# SolderIronTemp.net
KiCad netlist of a schematic drawn in Altium Designer
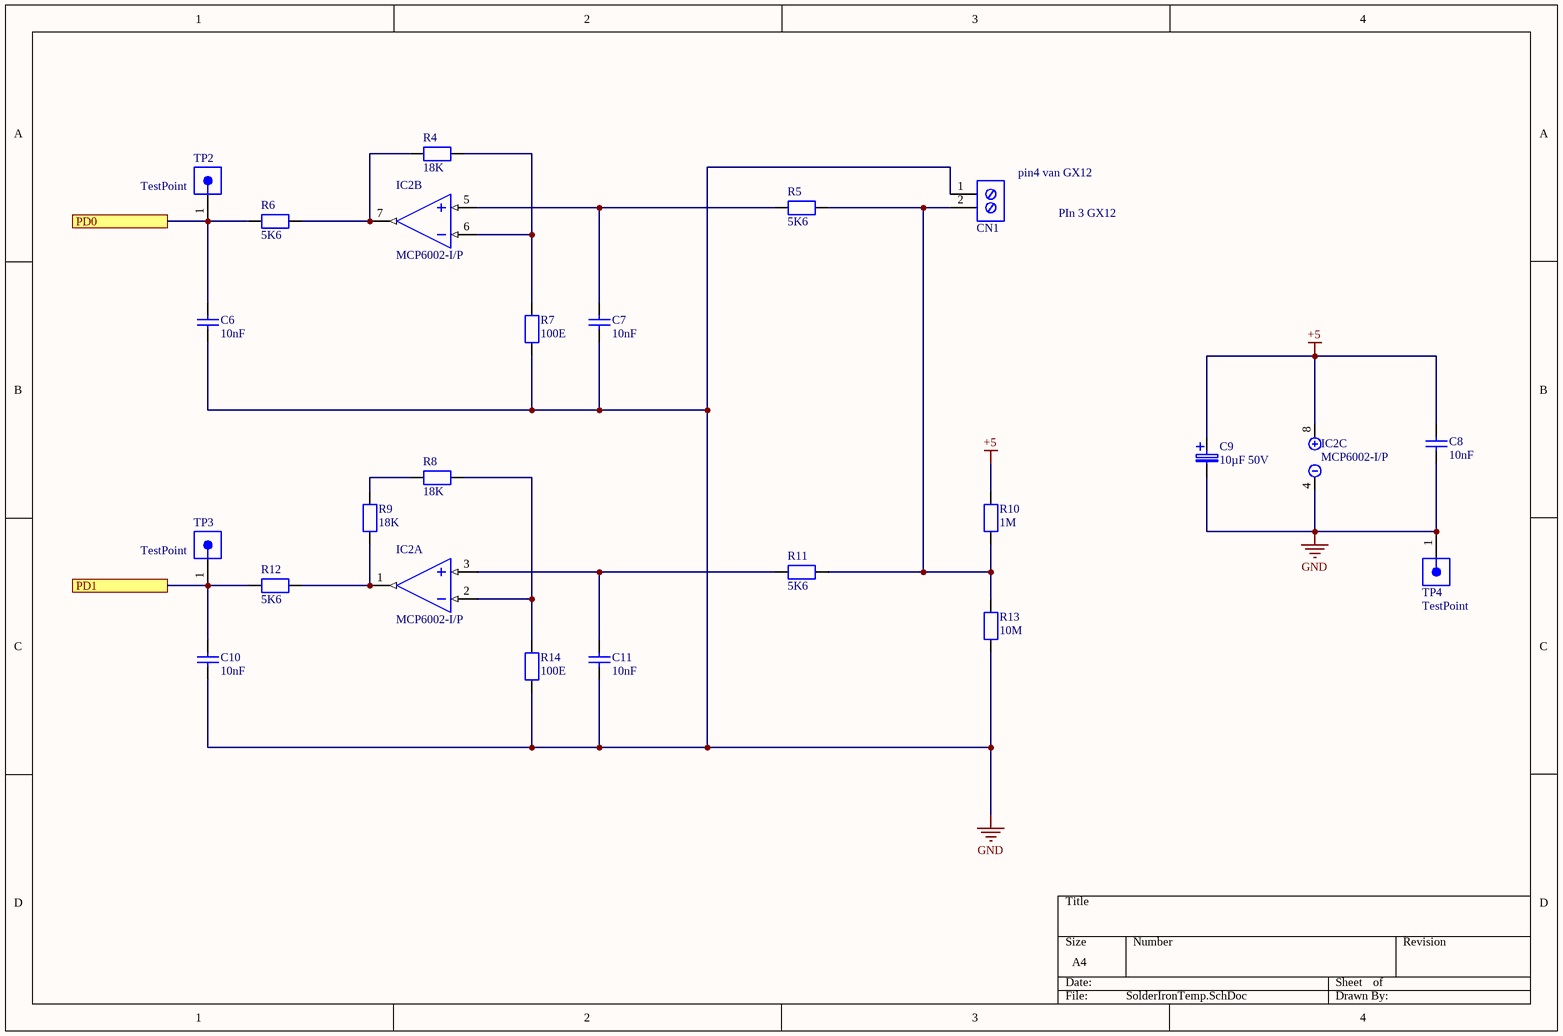
[diagram p0: SolderIronTemp.SchDoc]

(export (version "E")
  (design (tool "Eeschema 10.0.6"))
  (components
    (comp (ref "C6")
      (value "10nF")
      (footprint "CAPC2012X88N")
      (fields (field (name "MANUFACTURER") "Kemet") (field (name "PART NUMBER") "C0402C104K4RACTU"))
      (libsource (lib "SolderStation") (part "Capacitor ceramic 0805"))
    )
    (comp (ref "C7")
      (value "10nF")
      (footprint "CAPC2012X88N")
      (fields (field (name "MANUFACTURER") "Kemet") (field (name "PART NUMBER") "C0402C104K4RACTU"))
      (libsource (lib "SolderStation") (part "Capacitor ceramic 0805"))
    )
    (comp (ref "C8")
      (value "10nF")
      (footprint "CAPC2012X88N")
      (fields (field (name "MANUFACTURER") "Kemet") (field (name "PART NUMBER") "C0402C104K4RACTU"))
      (libsource (lib "SolderStation") (part "Capacitor ceramic 0805"))
    )
    (comp (ref "C9")
      (value "10µF 50V")
      (footprint "TAP106M050BRW")
      (description "Tantalum Capacitors - Solid Leaded 50V 10uF 20% ESR=1.6 Ohm TAP106M050BRW")
      (fields
        (field (name "MOUSER PART NUMBER") "581-TAP106M050BRW")
        (field (name "MANUFACTURER_PART_NUMBER") "TAP106M050BRW")
      )
      (libsource (lib "SolderStation") (part "capacitor THT radial tantalum"))
    )
    (comp (ref "C10")
      (value "10nF")
      (footprint "CAPC2012X88N")
      (fields (field (name "MANUFACTURER") "Kemet") (field (name "PART NUMBER") "C0402C104K4RACTU"))
      (libsource (lib "SolderStation") (part "Capacitor ceramic 0805"))
    )
    (comp (ref "C11")
      (value "10nF")
      (footprint "CAPC2012X88N")
      (fields (field (name "MANUFACTURER") "Kemet") (field (name "PART NUMBER") "C0402C104K4RACTU"))
      (libsource (lib "SolderStation") (part "Capacitor ceramic 0805"))
    )
    (comp (ref "CN1")
      (value "Printkroonsteen 2 POL")
      (footprint "Printkroonsteen 2pin")
      (description "Printkroonsteen 2 PO L1716020000")
      (fields
        (field (name "MANUFACTURER_PART_NUMBER") "1716020000")
        (field (name "MOUSER PART NUMBER") "470-1716020000")
      )
      (libsource (lib "SolderStation") (part "printkroonsteen 1 X 2"))
    )
    (comp (ref "IC2")
      (value "MCP6002-I/P")
      (footprint "PDIP300-P8")
      (description "Dual opamp")
      (libsource (lib "SolderStation") (part "CMP-0187-00119-3"))
    )
    (comp (ref "R4")
      (value "18K")
      (footprint "RESC2012X50N")
      (fields (field (name "MANUFACTURER") "Vishay Dale") (field (name "PART NUMBER") "CRCW08050000Z0EA"))
      (libsource (lib "SolderStation") (part "resistor 0805"))
    )
    (comp (ref "R5")
      (value "5K6")
      (footprint "RESC2012X50N")
      (fields (field (name "MANUFACTURER") "Vishay Dale") (field (name "PART NUMBER") "CRCW08050000Z0EA"))
      (libsource (lib "SolderStation") (part "resistor 0805"))
    )
    (comp (ref "R6")
      (value "5K6")
      (footprint "RESC2012X50N")
      (fields (field (name "MANUFACTURER") "Vishay Dale") (field (name "PART NUMBER") "CRCW08050000Z0EA"))
      (libsource (lib "SolderStation") (part "resistor 0805"))
    )
    (comp (ref "R7")
      (value "100E")
      (footprint "RESC2012X50N")
      (fields (field (name "MANUFACTURER") "Vishay Dale") (field (name "PART NUMBER") "CRCW08050000Z0EA"))
      (libsource (lib "SolderStation") (part "resistor 0805"))
    )
    (comp (ref "R8")
      (value "18K")
      (footprint "RESC2012X50N")
      (fields (field (name "MANUFACTURER") "Vishay Dale") (field (name "PART NUMBER") "CRCW08050000Z0EA"))
      (libsource (lib "SolderStation") (part "resistor 0805"))
    )
    (comp (ref "R9")
      (value "18K")
      (footprint "RESC2012X50N")
      (fields (field (name "MANUFACTURER") "Vishay Dale") (field (name "PART NUMBER") "CRCW08050000Z0EA"))
      (libsource (lib "SolderStation") (part "resistor 0805"))
    )
    (comp (ref "R10")
      (value "1M")
      (footprint "RESC2012X50N")
      (fields (field (name "MANUFACTURER") "Vishay Dale") (field (name "PART NUMBER") "CRCW08050000Z0EA"))
      (libsource (lib "SolderStation") (part "resistor 0805"))
    )
    (comp (ref "R11")
      (value "5K6")
      (footprint "RESC2012X50N")
      (fields (field (name "MANUFACTURER") "Vishay Dale") (field (name "PART NUMBER") "CRCW08050000Z0EA"))
      (libsource (lib "SolderStation") (part "resistor 0805"))
    )
    (comp (ref "R12")
      (value "5K6")
      (footprint "RESC2012X50N")
      (fields (field (name "MANUFACTURER") "Vishay Dale") (field (name "PART NUMBER") "CRCW08050000Z0EA"))
      (libsource (lib "SolderStation") (part "resistor 0805"))
    )
    (comp (ref "R13")
      (value "10M")
      (footprint "RESC2012X50N")
      (fields (field (name "MANUFACTURER") "Vishay Dale") (field (name "PART NUMBER") "CRCW08050000Z0EA"))
      (libsource (lib "SolderStation") (part "resistor 0805"))
    )
    (comp (ref "R14")
      (value "100E")
      (footprint "RESC2012X50N")
      (fields (field (name "MANUFACTURER") "Vishay Dale") (field (name "PART NUMBER") "CRCW08050000Z0EA"))
      (libsource (lib "SolderStation") (part "resistor 0805"))
    )
    (comp (ref "TP2")
      (value "TestPoint")
      (footprint "61300111121")
      (libsource (lib "SolderStation") (part "TestPoint"))
    )
    (comp (ref "TP3")
      (value "TestPoint")
      (footprint "61300111121")
      (libsource (lib "SolderStation") (part "TestPoint"))
    )
    (comp (ref "TP4")
      (value "TestPoint")
      (footprint "61300111121")
      (libsource (lib "SolderStation") (part "TestPoint"))
    )
  )
  (nets
    (net (code "1") (name "+5") (class "Default")
      (node (ref "C8") (pin "2") (pinfunction "2_2") (pintype "passive"))
      (node (ref "C9") (pin "1") (pinfunction "1_1") (pintype "passive"))
      (node (ref "IC2") (pin "8") (pinfunction "8_8") (pintype "passive"))
      (node (ref "R10") (pin "2") (pinfunction "2_2") (pintype "passive"))
    )
    (net (code "2") (name "/PD0") (class "Default")
      (node (ref "C6") (pin "2") (pinfunction "2_2") (pintype "passive"))
      (node (ref "R6") (pin "1") (pinfunction "1_1") (pintype "passive"))
      (node (ref "TP2") (pin "1") (pinfunction "1_1") (pintype "passive"))
    )
    (net (code "3") (name "/PD1") (class "Default")
      (node (ref "C10") (pin "2") (pinfunction "2_2") (pintype "passive"))
      (node (ref "R12") (pin "1") (pinfunction "1_1") (pintype "passive"))
      (node (ref "TP3") (pin "1") (pinfunction "1_1") (pintype "passive"))
    )
    (net (code "4") (name "GND") (class "Default")
      (node (ref "C10") (pin "1") (pinfunction "1_1") (pintype "passive"))
      (node (ref "C11") (pin "1") (pinfunction "1_1") (pintype "passive"))
      (node (ref "C6") (pin "1") (pinfunction "1_1") (pintype "passive"))
      (node (ref "C7") (pin "1") (pinfunction "1_1") (pintype "passive"))
      (node (ref "C8") (pin "1") (pinfunction "1_1") (pintype "passive"))
      (node (ref "C9") (pin "2") (pinfunction "2_2") (pintype "passive"))
      (node (ref "CN1") (pin "1") (pinfunction "1_1") (pintype "passive"))
      (node (ref "IC2") (pin "4") (pinfunction "4_4") (pintype "passive"))
      (node (ref "R13") (pin "1") (pinfunction "1_1") (pintype "passive"))
      (node (ref "R14") (pin "1") (pinfunction "1_1") (pintype "passive"))
      (node (ref "R7") (pin "1") (pinfunction "1_1") (pintype "passive"))
      (node (ref "TP4") (pin "1") (pinfunction "1_1") (pintype "passive"))
    )
    (net (code "5") (name "Net-(CN1-Pad2)") (class "Default")
      (node (ref "CN1") (pin "2") (pinfunction "2_2") (pintype "passive"))
      (node (ref "R10") (pin "1") (pinfunction "1_1") (pintype "passive"))
      (node (ref "R11") (pin "2") (pinfunction "2_2") (pintype "passive"))
      (node (ref "R13") (pin "2") (pinfunction "2_2") (pintype "passive"))
      (node (ref "R5") (pin "2") (pinfunction "2_2") (pintype "passive"))
    )
    (net (code "6") (name "Net-(IC2A-VINA+)") (class "Default")
      (node (ref "C11") (pin "2") (pinfunction "2_2") (pintype "passive"))
      (node (ref "IC2") (pin "3") (pinfunction "VINA+_3") (pintype "input"))
      (node (ref "R11") (pin "1") (pinfunction "1_1") (pintype "passive"))
    )
    (net (code "7") (name "Net-(IC2A-VINA-)") (class "Default")
      (node (ref "IC2") (pin "2") (pinfunction "VINA-_2") (pintype "input"))
      (node (ref "R14") (pin "2") (pinfunction "2_2") (pintype "passive"))
      (node (ref "R8") (pin "2") (pinfunction "2_2") (pintype "passive"))
    )
    (net (code "8") (name "Net-(IC2A-VOUTA)") (class "Default")
      (node (ref "IC2") (pin "1") (pinfunction "VOUTA_1") (pintype "output"))
      (node (ref "R12") (pin "2") (pinfunction "2_2") (pintype "passive"))
      (node (ref "R9") (pin "1") (pinfunction "1_1") (pintype "passive"))
    )
    (net (code "9") (name "Net-(IC2B-VINB+)") (class "Default")
      (node (ref "C7") (pin "2") (pinfunction "2_2") (pintype "passive"))
      (node (ref "IC2") (pin "5") (pinfunction "VINB+_5") (pintype "input"))
      (node (ref "R5") (pin "1") (pinfunction "1_1") (pintype "passive"))
    )
    (net (code "10") (name "Net-(IC2B-VINB-)") (class "Default")
      (node (ref "IC2") (pin "6") (pinfunction "VINB-_6") (pintype "input"))
      (node (ref "R4") (pin "2") (pinfunction "2_2") (pintype "passive"))
      (node (ref "R7") (pin "2") (pinfunction "2_2") (pintype "passive"))
    )
    (net (code "11") (name "Net-(IC2B-VOUTB)") (class "Default")
      (node (ref "IC2") (pin "7") (pinfunction "VOUTB_7") (pintype "output"))
      (node (ref "R4") (pin "1") (pinfunction "1_1") (pintype "passive"))
      (node (ref "R6") (pin "2") (pinfunction "2_2") (pintype "passive"))
    )
    (net (code "12") (name "Net-(R8-Pad1)") (class "Default")
      (node (ref "R8") (pin "1") (pinfunction "1_1") (pintype "passive"))
      (node (ref "R9") (pin "2") (pinfunction "2_2") (pintype "passive"))
    )
  )
)
